# CAN_Schematic.net
KiCad netlist of a schematic drawn in Altium Designer
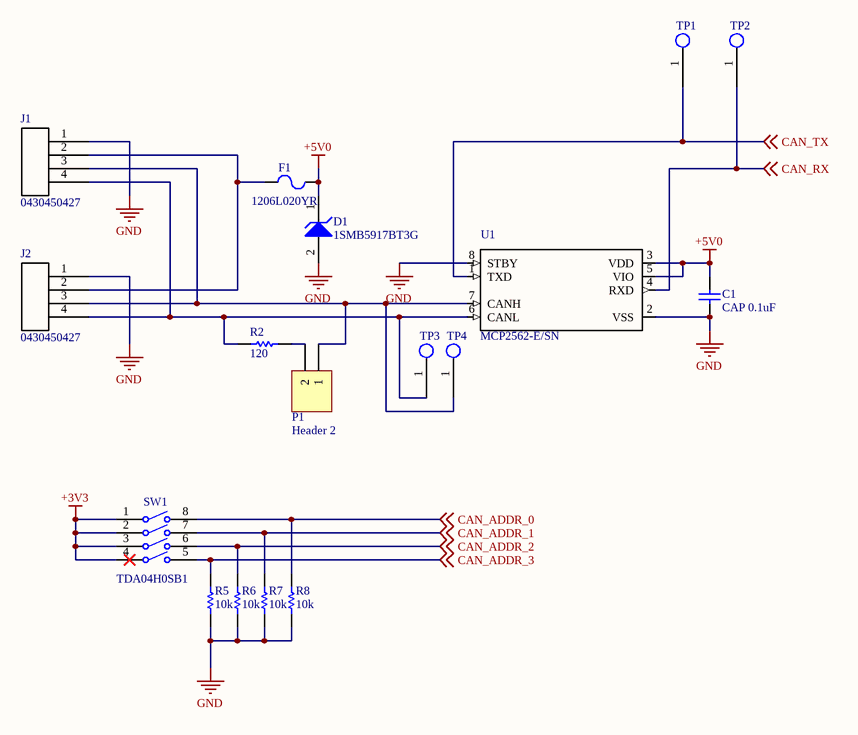
[diagram p0: CAN Schematic.SchDoc]

(export (version "E")
  (design (tool "Eeschema 10.0.6"))
  (components
    (comp (ref "C1")
      (value "CAP 0.1uF")
      (footprint "CAPC0805(2012)75_L")
      (description "CAP 2.7pF 50V ±0.1pF 0805 (2012 Metric) Thickness 0.75mm SMD")
      (fields (field (name "TOLERANCE") "Â±0.1pF"))
      (libsource (lib "Integrated_Library - 12.01.19 - 13.05") (part "CMP-1036-00339-1"))
    )
    (comp (ref "D1")
      (value "1SMB5917BT3G")
      (footprint "ONSC-SMB-2-403A-03_H_V")
      (description "3 W Zener Voltage Regulator, 2-Pin SMB, Pb-Free, Tape and Reel")
      (fields (field (name "MANUFACTURER") "On Semiconductor"))
      (libsource (lib "Husky Robotics Standard Library 2019-2020") (part "CMP-1060-00195-1"))
    )
    (comp (ref "F1")
      (value "1206L020YR")
      (footprint "LFUS-1206L020YR_V")
      (description "PTC Resettable Fuse, 100 A, 0.6W, -40 to 85 degC, 2-Pin SMD, RoHS, Tape and Reel")
      (fields (field (name "MANUFACTURER") "Littelfuse"))
      (libsource (lib "Altium Content Vault") (part "FUSE-2"))
    )
    (comp (ref "J1")
      (value "0430450427")
      (footprint "0430450427")
      (description "Molex micro-fit 3.0 dual row header. P/N 0430450427")
      (libsource (lib "Molex Micro-Fit 3.0") (part "0430450427-Single row schematic"))
    )
    (comp (ref "J2")
      (value "0430450427")
      (footprint "0430450427")
      (description "Molex micro-fit 3.0 dual row header. P/N 0430450427")
      (libsource (lib "Molex Micro-Fit 3.0") (part "0430450427-Single row schematic"))
    )
    (comp (ref "P1")
      (value "Header 2")
      (footprint "HDR1X2")
      (description "Header, 2-Pin")
      (fields (field (name "PUBLISHER") "Altium Limited"))
      (libsource (lib "Miscellaneous Connectors") (part "Header 2"))
    )
    (comp (ref "R2")
      (value "120")
      (footprint "RESC2013X70X40LL20T20")
      (description "RES SMD 150K OHM 1% 1/8W 0805")
      (fields (field (name "MANUFACTURER") "Panasonic") (field (name "PART NUMBER") "ERJ-6ENF1503V"))
      (libsource (lib "Altium Content Vault") (part "RES"))
    )
    (comp (ref "R5")
      (value "10k")
      (footprint "RESC2013X70X40LL20T20")
      (description "RES SMD 150K OHM 1% 1/8W 0805")
      (fields (field (name "MANUFACTURER") "Panasonic") (field (name "PART NUMBER") "ERJ-6ENF1503V"))
      (libsource (lib "Altium Content Vault") (part "RES"))
    )
    (comp (ref "R6")
      (value "10k")
      (footprint "RESC2013X70X40LL20T20")
      (description "RES SMD 150K OHM 1% 1/8W 0805")
      (fields (field (name "MANUFACTURER") "Panasonic") (field (name "PART NUMBER") "ERJ-6ENF1503V"))
      (libsource (lib "Altium Content Vault") (part "RES"))
    )
    (comp (ref "R7")
      (value "10k")
      (footprint "RESC2013X70X40LL20T20")
      (description "RES SMD 150K OHM 1% 1/8W 0805")
      (fields (field (name "MANUFACTURER") "Panasonic") (field (name "PART NUMBER") "ERJ-6ENF1503V"))
      (libsource (lib "Altium Content Vault") (part "RES"))
    )
    (comp (ref "R8")
      (value "10k")
      (footprint "RESC2013X70X40LL20T20")
      (description "RES SMD 150K OHM 1% 1/8W 0805")
      (fields (field (name "MANUFACTURER") "Panasonic") (field (name "PART NUMBER") "ERJ-6ENF1503V"))
      (libsource (lib "Altium Content Vault") (part "RES"))
    )
    (comp (ref "SW1")
      (value "TDA04H0SB1")
      (footprint "CKCP-TDA04H0SB1R_V")
      (libsource (lib "Husky Robotics Standard Library 2019-2020") (part "SMD Half-Pitch Dip Switch Array"))
    )
    (comp (ref "TP1")
      (value "Test Point")
      (footprint "Test Point Through-hole")
      (libsource (lib "Husky Robotics Standard Library 2019-2020") (part "Test Point"))
    )
    (comp (ref "TP2")
      (value "Test Point")
      (footprint "Test Point Through-hole")
      (libsource (lib "Husky Robotics Standard Library 2019-2020") (part "Test Point"))
    )
    (comp (ref "TP3")
      (value "Test Point")
      (footprint "Test Point Through-hole")
      (libsource (lib "Husky Robotics Standard Library 2019-2020") (part "Test Point"))
    )
    (comp (ref "TP4")
      (value "Test Point")
      (footprint "Test Point Through-hole")
      (libsource (lib "Husky Robotics Standard Library 2019-2020") (part "Test Point"))
    )
    (comp (ref "U1")
      (value "MCP2562-E/SN")
      (footprint "SOIC127P600X175-8N")
      (description "Microchip MCP2562-E/SN, CAN Transceiver 1MBps 1-channel IEC 61000-4-2, 8-Pin SOIC")
      (fields (field (name "MF") "Microchip"))
      (libsource (lib "MCP2562-E_SN") (part "MCP2562-E/SN"))
    )
  )
  (nets
    (net (code "1") (name "+3V3") (class "Default")
      (node (ref "SW1") (pin "1") (pinfunction "1_1") (pintype "passive"))
      (node (ref "SW1") (pin "2") (pinfunction "2_2") (pintype "passive"))
      (node (ref "SW1") (pin "3") (pinfunction "3_3") (pintype "passive"))
      (node (ref "SW1") (pin "4") (pinfunction "4_4") (pintype "passive"))
    )
    (net (code "2") (name "+5V0") (class "Default")
      (node (ref "C1") (pin "2") (pinfunction "2_2") (pintype "passive"))
      (node (ref "D1") (pin "1") (pinfunction "K_1") (pintype "passive"))
      (node (ref "F1") (pin "2") (pinfunction "2_2") (pintype "passive"))
      (node (ref "U1") (pin "3") (pinfunction "VDD_3") (pintype "power_in"))
      (node (ref "U1") (pin "5") (pinfunction "VIO_5") (pintype "power_in"))
    )
    (net (code "3") (name "CAN_ADDR_0") (class "Default")
      (node (ref "R8") (pin "1") (pinfunction "1_1") (pintype "passive"))
      (node (ref "SW1") (pin "8") (pinfunction "8_8") (pintype "passive"))
    )
    (net (code "4") (name "CAN_ADDR_1") (class "Default")
      (node (ref "R7") (pin "1") (pinfunction "1_1") (pintype "passive"))
      (node (ref "SW1") (pin "7") (pinfunction "7_7") (pintype "passive"))
    )
    (net (code "5") (name "CAN_ADDR_2") (class "Default")
      (node (ref "R6") (pin "1") (pinfunction "1_1") (pintype "passive"))
      (node (ref "SW1") (pin "6") (pinfunction "6_6") (pintype "passive"))
    )
    (net (code "6") (name "CAN_ADDR_3") (class "Default")
      (node (ref "R5") (pin "1") (pinfunction "1_1") (pintype "passive"))
      (node (ref "SW1") (pin "5") (pinfunction "5_5") (pintype "passive"))
    )
    (net (code "7") (name "CAN_RX") (class "Default")
      (node (ref "TP2") (pin "1") (pinfunction "1_1") (pintype "passive"))
      (node (ref "U1") (pin "4") (pinfunction "RXD_4") (pintype "output"))
    )
    (net (code "8") (name "CAN_TX") (class "Default")
      (node (ref "TP1") (pin "1") (pinfunction "1_1") (pintype "passive"))
      (node (ref "U1") (pin "1") (pinfunction "TXD_1") (pintype "input"))
    )
    (net (code "9") (name "GND") (class "Default")
      (node (ref "C1") (pin "1") (pinfunction "1_1") (pintype "passive"))
      (node (ref "D1") (pin "2") (pinfunction "A_2") (pintype "passive"))
      (node (ref "J1") (pin "1") (pintype "passive"))
      (node (ref "J2") (pin "1") (pintype "passive"))
      (node (ref "R5") (pin "2") (pinfunction "2_2") (pintype "passive"))
      (node (ref "R6") (pin "2") (pinfunction "2_2") (pintype "passive"))
      (node (ref "R7") (pin "2") (pinfunction "2_2") (pintype "passive"))
      (node (ref "R8") (pin "2") (pinfunction "2_2") (pintype "passive"))
      (node (ref "U1") (pin "2") (pinfunction "VSS_2") (pintype "power_in"))
      (node (ref "U1") (pin "8") (pinfunction "STBY_8") (pintype "input"))
    )
    (net (code "10") (name "Net-(F1-Pad1)") (class "Default")
      (node (ref "F1") (pin "1") (pinfunction "1_1") (pintype "passive"))
      (node (ref "J1") (pin "2") (pintype "passive"))
      (node (ref "J2") (pin "2") (pintype "passive"))
    )
    (net (code "11") (name "Net-(P1-Pad2)") (class "Default")
      (node (ref "P1") (pin "2") (pinfunction "2_2") (pintype "passive"))
      (node (ref "R2") (pin "1") (pinfunction "1_1") (pintype "passive"))
    )
    (net (code "12") (name "Net-(U1-CANH)") (class "Default")
      (node (ref "J1") (pin "3") (pintype "passive"))
      (node (ref "J2") (pin "3") (pintype "passive"))
      (node (ref "P1") (pin "1") (pinfunction "1_1") (pintype "passive"))
      (node (ref "TP4") (pin "1") (pinfunction "1_1") (pintype "passive"))
      (node (ref "U1") (pin "7") (pinfunction "CANH_7") (pintype "input"))
    )
    (net (code "13") (name "Net-(U1-CANL)") (class "Default")
      (node (ref "J1") (pin "4") (pintype "passive"))
      (node (ref "J2") (pin "4") (pintype "passive"))
      (node (ref "R2") (pin "2") (pinfunction "2_2") (pintype "passive"))
      (node (ref "TP3") (pin "1") (pinfunction "1_1") (pintype "passive"))
      (node (ref "U1") (pin "6") (pinfunction "CANL_6") (pintype "input"))
    )
  )
)
